# range_valid_stretching.net
KiCad netlist of a schematic drawn in Altium Designer
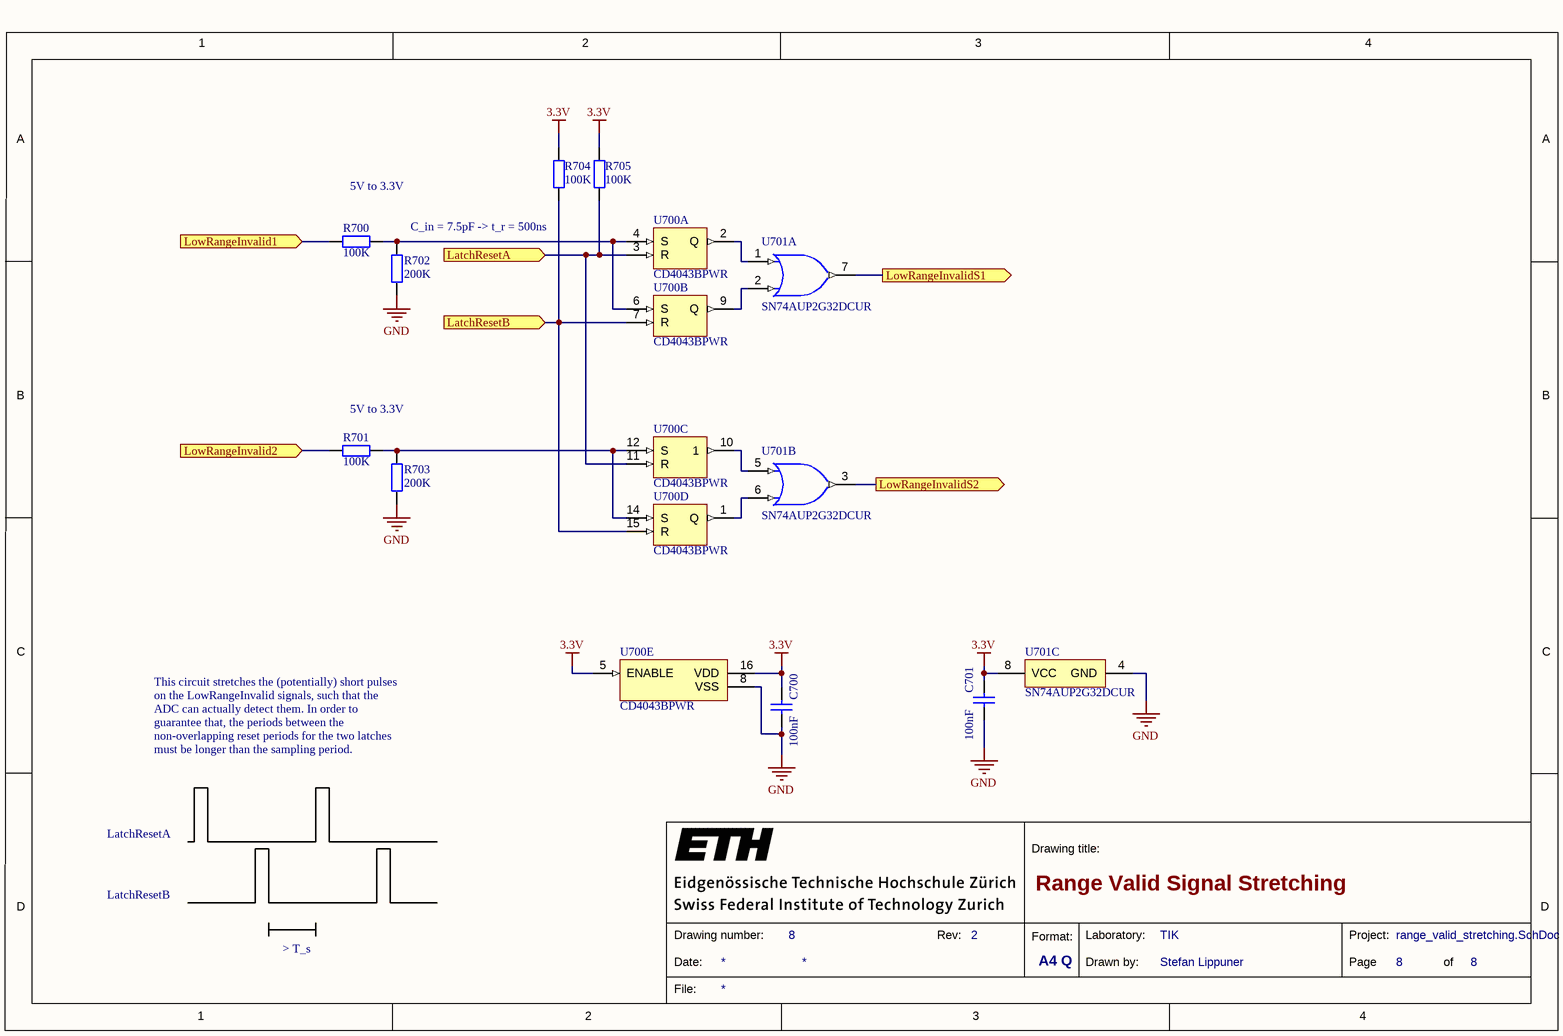
[diagram p0: range_valid_stretching.SchDoc]

(export (version "E")
  (design (tool "Eeschema 10.0.6"))
  (components
    (comp (ref "C700")
      (value "100nF")
      (footprint "CAPC0402(1005)60_L")
      (description "CAP 100nF 16V -20% to +80% 0402 (1005 Metric) Thickness 0.6mm SMD")
      (fields (field (name "TOLERANCE") "-20% to +80%"))
      (libsource (lib "Altium Content Vault") (part "CMP-1034-02071-1"))
    )
    (comp (ref "C701")
      (value "100nF")
      (footprint "CAPC0402(1005)60_L")
      (description "CAP 100nF 16V -20% to +80% 0402 (1005 Metric) Thickness 0.6mm SMD")
      (fields (field (name "TOLERANCE") "-20% to +80%"))
      (libsource (lib "Altium Content Vault") (part "CMP-1034-02071-1"))
    )
    (comp (ref "R700")
      (value "100K")
      (footprint "RESC0402(1005)_L")
      (description "100K 0.063W 1% 0402 (1005 Metric)  SMD")
      (fields (field (name "POWER") "0.063 W") (field (name "TOLERANCE") "1 %"))
      (libsource (lib "Altium Content Vault") (part "CMP-1011-00736"))
    )
    (comp (ref "R701")
      (value "100K")
      (footprint "RESC0402(1005)_L")
      (description "100K 0.063W 1% 0402 (1005 Metric)  SMD")
      (fields (field (name "POWER") "0.063 W") (field (name "TOLERANCE") "1 %"))
      (libsource (lib "Altium Content Vault") (part "CMP-1011-00736"))
    )
    (comp (ref "R702")
      (value "200K")
      (footprint "RESC0402(1005)_L")
      (description "200K 0.063W 5% 0402 (1005 Metric)  SMD")
      (fields (field (name "TOLERANCE") "5 %") (field (name "POWER") "0.063 W"))
      (libsource (lib "Altium Content Vault") (part "CMP-1011-00129-1"))
    )
    (comp (ref "R703")
      (value "200K")
      (footprint "RESC0402(1005)_L")
      (description "200K 0.063W 5% 0402 (1005 Metric)  SMD")
      (fields (field (name "TOLERANCE") "5 %") (field (name "POWER") "0.063 W"))
      (libsource (lib "Altium Content Vault") (part "CMP-1011-00129-1"))
    )
    (comp (ref "R704")
      (value "100K")
      (footprint "RESC0402(1005)_L")
      (description "100K 0.063W 1% 0402 (1005 Metric)  SMD")
      (fields (field (name "POWER") "0.063 W") (field (name "TOLERANCE") "1 %"))
      (libsource (lib "") (part "CMP-1011-00736_1"))
    )
    (comp (ref "R705")
      (value "100K")
      (footprint "RESC0402(1005)_L")
      (description "100K 0.063W 1% 0402 (1005 Metric)  SMD")
      (fields (field (name "POWER") "0.063 W") (field (name "TOLERANCE") "1 %"))
      (libsource (lib "") (part "CMP-1011-00736_1"))
    )
    (comp (ref "U700")
      (value "CD4043BPWR")
      (footprint "TSSOP-16_L")
      (description "IC NOR R/S LTCH 3ST QUAD 16TSSOP")
      (fields (field (name "MANUFACTURER") "Texas Instruments"))
      (libsource (lib "ETHZ Vault") (part "CD4043B"))
    )
    (comp (ref "U701")
      (value "SN74AUP2G32DCUR")
      (footprint "DCU0008A_L")
      (description "Low-Power Dual 2-Input Positive-OR Gate, DCU0008A, LARGE T&R")
      (fields
        (field (name "MANUFACTURER") "Texas Instruments")
        (field (name "GENERIC PART NUMBER") "SN74AUP2G32")
      )
      (libsource (lib "Altium Content Vault") (part "TI-SN74XXX2G32-8"))
    )
  )
  (nets
    (net (code "1") (name "/LatchResetA") (class "Default")
      (node (ref "R705") (pin "1") (pinfunction "1_1") (pintype "passive"))
      (node (ref "U700") (pin "11") (pinfunction "R_11") (pintype "input"))
      (node (ref "U700") (pin "3") (pinfunction "R_3") (pintype "input"))
    )
    (net (code "2") (name "/LatchResetB") (class "Default")
      (node (ref "R704") (pin "1") (pinfunction "1_1") (pintype "passive"))
      (node (ref "U700") (pin "15") (pinfunction "R_15") (pintype "input"))
      (node (ref "U700") (pin "7") (pinfunction "R_7") (pintype "input"))
    )
    (net (code "3") (name "/LowRangeInvalid1") (class "Default")
      (node (ref "R700") (pin "1") (pinfunction "1_1") (pintype "passive"))
    )
    (net (code "4") (name "/LowRangeInvalid2") (class "Default")
      (node (ref "R701") (pin "1") (pinfunction "1_1") (pintype "passive"))
    )
    (net (code "5") (name "/LowRangeInvalidS1") (class "Default")
      (node (ref "U701") (pin "7") (pinfunction "1Y_7") (pintype "output"))
    )
    (net (code "6") (name "/LowRangeInvalidS2") (class "Default")
      (node (ref "U701") (pin "3") (pinfunction "2Y_3") (pintype "output"))
    )
    (net (code "7") (name "3.3V") (class "Default")
      (node (ref "C700") (pin "2") (pinfunction "2_2") (pintype "passive"))
      (node (ref "C701") (pin "2") (pinfunction "2_2") (pintype "passive"))
      (node (ref "R704") (pin "2") (pinfunction "2_2") (pintype "passive"))
      (node (ref "R705") (pin "2") (pinfunction "2_2") (pintype "passive"))
      (node (ref "U700") (pin "16") (pinfunction "VDD_16") (pintype "power_in"))
      (node (ref "U700") (pin "5") (pinfunction "ENABLE_5") (pintype "input"))
      (node (ref "U701") (pin "8") (pinfunction "VCC_8") (pintype "power_in"))
    )
    (net (code "8") (name "GND") (class "Default")
      (node (ref "C700") (pin "1") (pinfunction "1_1") (pintype "passive"))
      (node (ref "C701") (pin "1") (pinfunction "1_1") (pintype "passive"))
      (node (ref "R702") (pin "1") (pinfunction "1_1") (pintype "passive"))
      (node (ref "R703") (pin "1") (pinfunction "1_1") (pintype "passive"))
      (node (ref "U700") (pin "8") (pinfunction "VSS_8") (pintype "power_in"))
      (node (ref "U701") (pin "4") (pinfunction "GND_4") (pintype "power_in"))
    )
    (net (code "9") (name "Net-(U700A-Q)") (class "Default")
      (node (ref "U700") (pin "2") (pinfunction "Q_2") (pintype "output"))
      (node (ref "U701") (pin "1") (pinfunction "1A_1") (pintype "input"))
    )
    (net (code "10") (name "Net-(U700A-S)") (class "Default")
      (node (ref "R700") (pin "2") (pinfunction "2_2") (pintype "passive"))
      (node (ref "R702") (pin "2") (pinfunction "2_2") (pintype "passive"))
      (node (ref "U700") (pin "4") (pinfunction "S_4") (pintype "input"))
      (node (ref "U700") (pin "6") (pinfunction "S_6") (pintype "input"))
    )
    (net (code "11") (name "Net-(U700B-Q)") (class "Default")
      (node (ref "U700") (pin "9") (pinfunction "Q_9") (pintype "output"))
      (node (ref "U701") (pin "2") (pinfunction "1B_2") (pintype "input"))
    )
    (net (code "12") (name "Net-(U700C-1)") (class "Default")
      (node (ref "U700") (pin "10") (pinfunction "1_10") (pintype "output"))
      (node (ref "U701") (pin "5") (pinfunction "2A_5") (pintype "input"))
    )
    (net (code "13") (name "Net-(U700C-S)") (class "Default")
      (node (ref "R701") (pin "2") (pinfunction "2_2") (pintype "passive"))
      (node (ref "R703") (pin "2") (pinfunction "2_2") (pintype "passive"))
      (node (ref "U700") (pin "12") (pinfunction "S_12") (pintype "input"))
      (node (ref "U700") (pin "14") (pinfunction "S_14") (pintype "input"))
    )
    (net (code "14") (name "Net-(U700D-Q)") (class "Default")
      (node (ref "U700") (pin "1") (pinfunction "Q_1") (pintype "output"))
      (node (ref "U701") (pin "6") (pinfunction "2B_6") (pintype "input"))
    )
  )
)
